# dwm1000-breakout.net
KiCad netlist of a schematic drawn in EAGLE
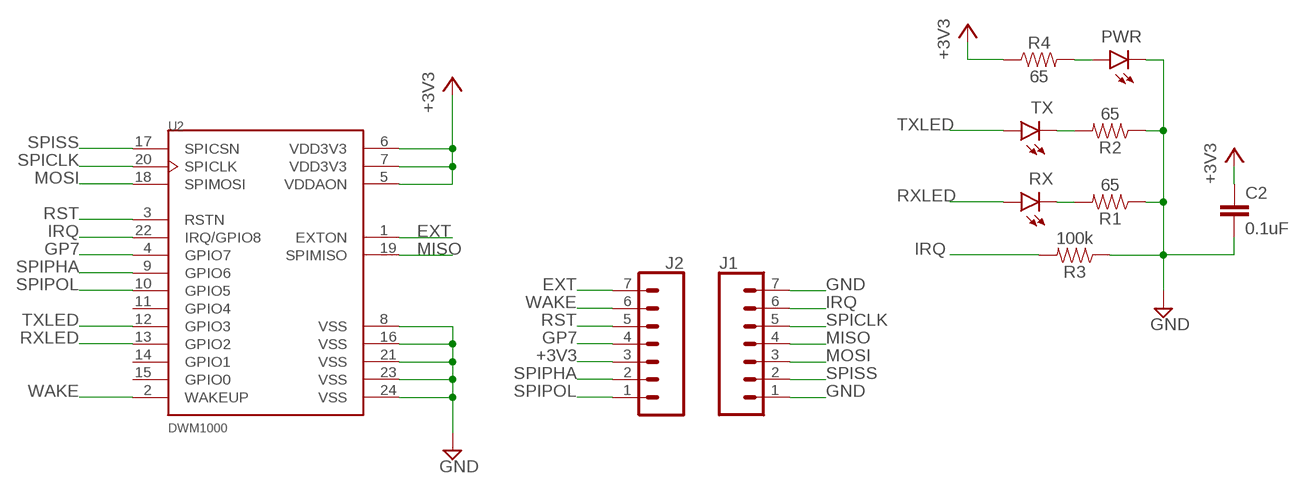
[diagram p0: schematic, sheet 1]

(export (version "E")
  (design (tool "Eeschema 10.0.6"))
  (components
    (comp (ref "C2")
      (value "0.1uF")
      (footprint "eagle-import:C1210")
      (fields (field (name "DIGIKEY_PARTNUM") "1276-2854-1-ND"))
      (libsource (lib "eagle-import") (part "CAPACITOR_NP_1210"))
    )
    (comp (ref "J1")
      (value "CONN_07LOCK")
      (footprint "eagle-import:1X07_LOCK")
      (fields (field (name "DIGIKEY_PARTNUM") "A26509-07-ND"))
      (libsource (lib "eagle-import") (part "CONN_07LOCK"))
    )
    (comp (ref "J2")
      (value "CONN_07LOCK")
      (footprint "eagle-import:1X07_LOCK")
      (fields (field (name "DIGIKEY_PARTNUM") "A26509-07-ND"))
      (libsource (lib "eagle-import") (part "CONN_07LOCK"))
    )
    (comp (ref "PWR")
      (value "GREEN")
      (footprint "eagle-import:LED-1206")
      (fields (field (name "DIGIKEY_PARTNUM") "350-2053-1-ND"))
      (libsource (lib "eagle-import") (part "LED-GREEN1206"))
    )
    (comp (ref "R1")
      (value "65")
      (footprint "eagle-import:1206")
      (fields (field (name "DIGIKEY_PARTNUM") "311-64.9FRCT-ND"))
      (libsource (lib "eagle-import") (part "RESISTOR1206"))
    )
    (comp (ref "R2")
      (value "65")
      (footprint "eagle-import:1206")
      (fields (field (name "DIGIKEY_PARTNUM") "311-64.9FRCT-ND"))
      (libsource (lib "eagle-import") (part "RESISTOR1206"))
    )
    (comp (ref "R3")
      (value "100k")
      (footprint "eagle-import:1206")
      (fields (field (name "DIGIKEY_PARTNUM") "311-100KERCT-ND"))
      (libsource (lib "eagle-import") (part "RESISTOR1206"))
    )
    (comp (ref "R4")
      (value "65")
      (footprint "eagle-import:1206")
      (fields (field (name "DIGIKEY_PARTNUM") "311-64.9FRCT-ND"))
      (libsource (lib "eagle-import") (part "RESISTOR1206"))
    )
    (comp (ref "RX")
      (value "GREEN")
      (footprint "eagle-import:LED-1206")
      (fields (field (name "DIGIKEY_PARTNUM") "350-2053-1-ND"))
      (libsource (lib "eagle-import") (part "LED-GREEN1206"))
    )
    (comp (ref "TX")
      (value "GREEN")
      (footprint "eagle-import:LED-1206")
      (libsource (lib "eagle-import") (part "LED-GREEN1206"))
    )
    (comp (ref "U2")
      (value "DWM1000")
      (footprint "eagle-import:XCVR_DWM1000")
      (fields (field (name "MF") "Decawave") (field (name "DIGIKEY_PARTNUM") "1479-1002-1-ND"))
      (libsource (lib "eagle-import") (part "DWM1000"))
    )
  )
  (nets
    (net (code "1") (name "+3V3") (class "Default")
      (node (ref "C2") (pin "P$1") (pinfunction "P$1_P$1") (pintype "passive"))
      (node (ref "J2") (pin "3") (pinfunction "3_3") (pintype "passive"))
      (node (ref "R4") (pin "1") (pinfunction "1_1") (pintype "passive"))
      (node (ref "U2") (pin "5") (pinfunction "VDDAON_5") (pintype "power_in"))
      (node (ref "U2") (pin "6") (pinfunction "VDD3V3_6") (pintype "power_in"))
      (node (ref "U2") (pin "7") (pinfunction "VDD3V3_7") (pintype "power_in"))
    )
    (net (code "2") (name "/EXT") (class "Default")
      (node (ref "J2") (pin "7") (pinfunction "7_7") (pintype "passive"))
      (node (ref "U2") (pin "1") (pinfunction "EXTON_1") (pintype "output"))
    )
    (net (code "3") (name "/GP7") (class "Default")
      (node (ref "J2") (pin "4") (pinfunction "4_4") (pintype "passive"))
      (node (ref "U2") (pin "4") (pinfunction "GPIO7_4") (pintype "bidirectional"))
    )
    (net (code "4") (name "/IRQ") (class "Default")
      (node (ref "J1") (pin "6") (pinfunction "6_6") (pintype "passive"))
      (node (ref "R3") (pin "2") (pinfunction "2_2") (pintype "passive"))
      (node (ref "U2") (pin "22") (pinfunction "IRQ/GPIO8_22") (pintype "bidirectional"))
    )
    (net (code "5") (name "/MISO") (class "Default")
      (node (ref "J1") (pin "4") (pinfunction "4_4") (pintype "passive"))
      (node (ref "U2") (pin "19") (pinfunction "SPIMISO_19") (pintype "output"))
    )
    (net (code "6") (name "/MOSI") (class "Default")
      (node (ref "J1") (pin "3") (pinfunction "3_3") (pintype "passive"))
      (node (ref "U2") (pin "18") (pinfunction "SPIMOSI_18") (pintype "input"))
    )
    (net (code "7") (name "/RST") (class "Default")
      (node (ref "J2") (pin "5") (pinfunction "5_5") (pintype "passive"))
      (node (ref "U2") (pin "3") (pinfunction "RSTN_3") (pintype "bidirectional"))
    )
    (net (code "8") (name "/RXLED") (class "Default")
      (node (ref "RX") (pin "A") (pinfunction "A_A") (pintype "passive"))
      (node (ref "U2") (pin "13") (pinfunction "GPIO2_13") (pintype "bidirectional"))
    )
    (net (code "9") (name "/SPICLK") (class "Default")
      (node (ref "J1") (pin "5") (pinfunction "5_5") (pintype "passive"))
      (node (ref "U2") (pin "20") (pinfunction "SPICLK_20") (pintype "input"))
    )
    (net (code "10") (name "/SPIPHA") (class "Default")
      (node (ref "J2") (pin "2") (pinfunction "2_2") (pintype "passive"))
      (node (ref "U2") (pin "9") (pinfunction "GPIO6_9") (pintype "bidirectional"))
    )
    (net (code "11") (name "/SPIPOL") (class "Default")
      (node (ref "J2") (pin "1") (pinfunction "1_1") (pintype "passive"))
      (node (ref "U2") (pin "10") (pinfunction "GPIO5_10") (pintype "bidirectional"))
    )
    (net (code "12") (name "/SPISS") (class "Default")
      (node (ref "J1") (pin "2") (pinfunction "2_2") (pintype "passive"))
      (node (ref "U2") (pin "17") (pinfunction "SPICSN_17") (pintype "input"))
    )
    (net (code "13") (name "/TXLED") (class "Default")
      (node (ref "TX") (pin "A") (pinfunction "A_A") (pintype "passive"))
      (node (ref "U2") (pin "12") (pinfunction "GPIO3_12") (pintype "bidirectional"))
    )
    (net (code "14") (name "/WAKE") (class "Default")
      (node (ref "J2") (pin "6") (pinfunction "6_6") (pintype "passive"))
      (node (ref "U2") (pin "2") (pinfunction "WAKEUP_2") (pintype "bidirectional"))
    )
    (net (code "15") (name "GND") (class "Default")
      (node (ref "C2") (pin "P$2") (pinfunction "P$2_P$2") (pintype "passive"))
      (node (ref "J1") (pin "1") (pinfunction "1_1") (pintype "passive"))
      (node (ref "J1") (pin "7") (pinfunction "7_7") (pintype "passive"))
      (node (ref "PWR") (pin "C") (pinfunction "C_C") (pintype "passive"))
      (node (ref "R1") (pin "1") (pinfunction "1_1") (pintype "passive"))
      (node (ref "R2") (pin "1") (pinfunction "1_1") (pintype "passive"))
      (node (ref "R3") (pin "1") (pinfunction "1_1") (pintype "passive"))
      (node (ref "U2") (pin "16") (pinfunction "VSS_16") (pintype "power_in"))
      (node (ref "U2") (pin "21") (pinfunction "VSS_21") (pintype "power_in"))
      (node (ref "U2") (pin "23") (pinfunction "VSS_23") (pintype "power_in"))
      (node (ref "U2") (pin "24") (pinfunction "VSS_24") (pintype "power_in"))
      (node (ref "U2") (pin "8") (pinfunction "VSS_8") (pintype "power_in"))
    )
    (net (code "16") (name "Net-(PWR-PadA)") (class "Default")
      (node (ref "PWR") (pin "A") (pinfunction "A_A") (pintype "passive"))
      (node (ref "R4") (pin "2") (pinfunction "2_2") (pintype "passive"))
    )
    (net (code "17") (name "Net-(R1-Pad2)") (class "Default")
      (node (ref "R1") (pin "2") (pinfunction "2_2") (pintype "passive"))
      (node (ref "RX") (pin "C") (pinfunction "C_C") (pintype "passive"))
    )
    (net (code "18") (name "Net-(R2-Pad2)") (class "Default")
      (node (ref "R2") (pin "2") (pinfunction "2_2") (pintype "passive"))
      (node (ref "TX") (pin "C") (pinfunction "C_C") (pintype "passive"))
    )
    (net (code "19") (name "unconnected-(U2-GPIO0-Pad15)") (class "Default")
      (node (ref "U2") (pin "15") (pinfunction "GPIO0_15") (pintype "bidirectional"))
    )
    (net (code "20") (name "unconnected-(U2-GPIO1-Pad14)") (class "Default")
      (node (ref "U2") (pin "14") (pinfunction "GPIO1_14") (pintype "bidirectional"))
    )
    (net (code "21") (name "unconnected-(U2-GPIO4-Pad11)") (class "Default")
      (node (ref "U2") (pin "11") (pinfunction "GPIO4_11") (pintype "bidirectional"))
    )
  )
)
